# rev_001.net
KiCad netlist of a schematic drawn in EAGLE
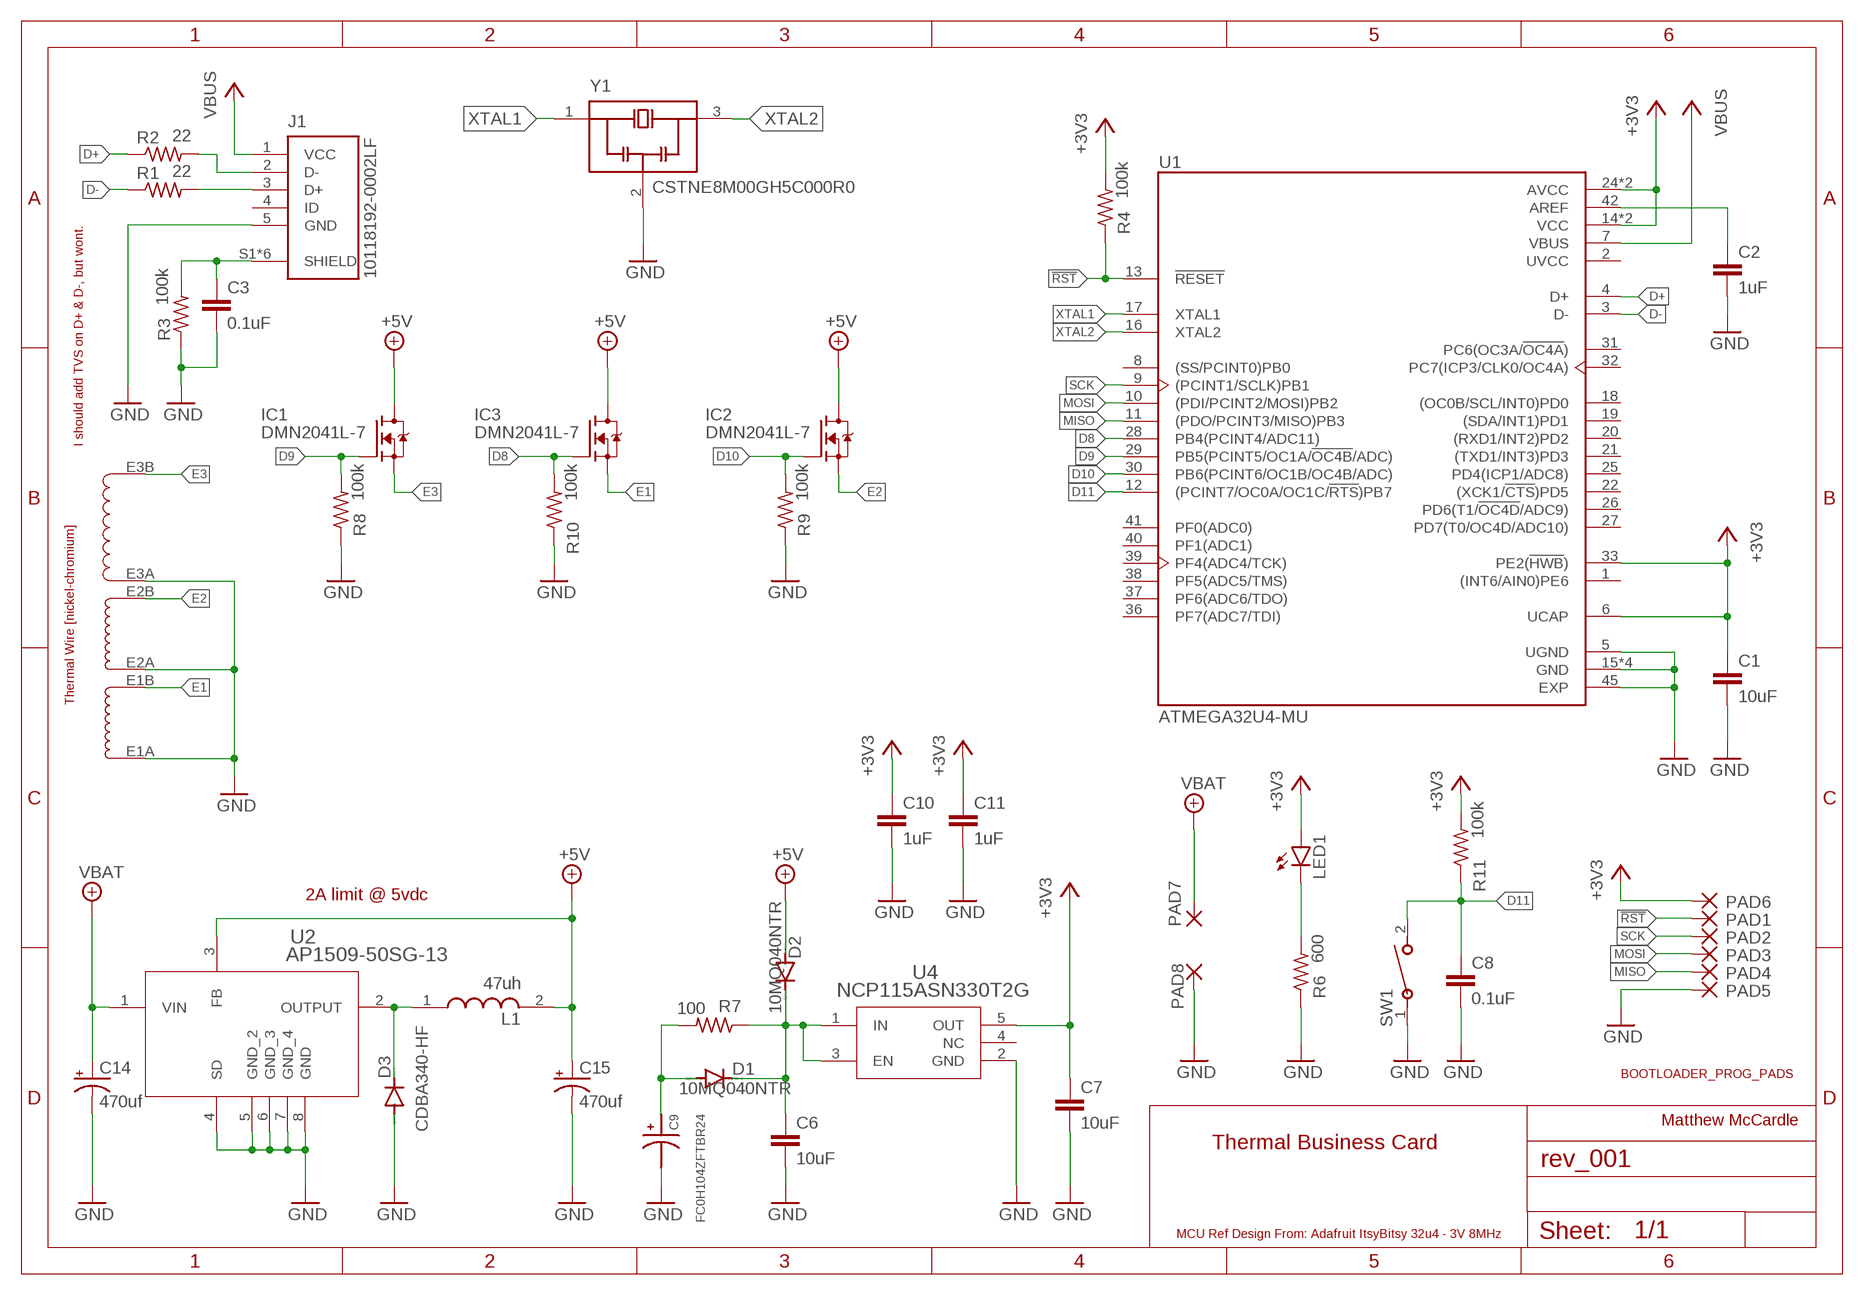
[diagram p0: schematic, sheet 1]

(export (version "E")
  (design (tool "Eeschema 10.0.6"))
  (components
    (comp (ref "C1")
      (value "10uF")
      (footprint "eagle-import:C0603")
      (libsource (lib "eagle-import") (part "C-EUC0603"))
    )
    (comp (ref "C2")
      (value "1uF")
      (footprint "eagle-import:C0603")
      (libsource (lib "eagle-import") (part "C-EUC0603"))
    )
    (comp (ref "C3")
      (value "0.1uF")
      (footprint "eagle-import:C0603")
      (libsource (lib "eagle-import") (part "C-EUC0603"))
    )
    (comp (ref "C6")
      (value "10uF")
      (footprint "eagle-import:C0603")
      (libsource (lib "eagle-import") (part "C-EUC0603"))
    )
    (comp (ref "C7")
      (value "10uF")
      (footprint "eagle-import:C0603")
      (libsource (lib "eagle-import") (part "C-EUC0603"))
    )
    (comp (ref "C8")
      (value "0.1uF")
      (footprint "eagle-import:C0603")
      (libsource (lib "eagle-import") (part "C-EUC0603"))
    )
    (comp (ref "C9")
      (value "FC0H104ZFTBR24")
      (footprint "eagle-import:CAPAE1080X580N")
      (fields (field (name "DIGI-KEY_PART_NUMBER") "399-10939-1-ND") (field (name "MF") "KEMET"))
      (libsource (lib "eagle-import") (part "FC0H104ZFTBR24"))
    )
    (comp (ref "C10")
      (value "1uF")
      (footprint "eagle-import:C0603")
      (libsource (lib "eagle-import") (part "C-EUC0603"))
    )
    (comp (ref "C11")
      (value "1uF")
      (footprint "eagle-import:C0603")
      (libsource (lib "eagle-import") (part "C-EUC0603"))
    )
    (comp (ref "C14")
      (value "470uf")
      (footprint "eagle-import:UD-4X5,8_NICHICON")
      (libsource (lib "eagle-import") (part "CPOL-USUD-4X5,8"))
    )
    (comp (ref "C15")
      (value "470uf")
      (footprint "eagle-import:UD-4X5,8_NICHICON")
      (libsource (lib "eagle-import") (part "CPOL-USUD-4X5,8"))
    )
    (comp (ref "D1")
      (value "10MQ040NTR")
      (footprint "eagle-import:DO-214AC")
      (libsource (lib "eagle-import") (part "DIODE-DO-214AC"))
    )
    (comp (ref "D2")
      (value "10MQ040NTR")
      (footprint "eagle-import:DO-214AC")
      (libsource (lib "eagle-import") (part "DIODE-DO-214AC"))
    )
    (comp (ref "D3")
      (value "CDBA340-HF")
      (footprint "eagle-import:DO-214AC")
      (libsource (lib "eagle-import") (part "DIODE-DO-214AC"))
    )
    (comp (ref "IC1")
      (value "DMN2041L-7")
      (footprint "eagle-import:SOT23")
      (libsource (lib "eagle-import") (part "DS31126"))
    )
    (comp (ref "IC2")
      (value "DMN2041L-7")
      (footprint "eagle-import:SOT23")
      (libsource (lib "eagle-import") (part "DS31126"))
    )
    (comp (ref "IC3")
      (value "DMN2041L-7")
      (footprint "eagle-import:SOT23")
      (libsource (lib "eagle-import") (part "DS31126"))
    )
    (comp (ref "J1")
      (value "10118192-0002LF")
      (footprint "eagle-import:AMPHENOL_10118192-0002LF")
      (fields (field (name "DIGI-KEY_PART_NUMBER") "609-5379-1-ND") (field (name "MF") "Amphenol ICC (FCI)"))
      (libsource (lib "eagle-import") (part "10118192-0002LF"))
    )
    (comp (ref "L1")
      (value "47uh")
      (footprint "eagle-import:WUERTH_ELEKTRONIK_7447714470_0")
      (fields (field (name "MF") "Wuerth Elektronik") (field (name "MPN") "7447714470"))
      (libsource (lib "eagle-import") (part "WUERTH_ELEKTRONIK_7447714470WUERTH_ELEKTRONIK_7447714470_0_0"))
    )
    (comp (ref "LED1")
      (value "LEDSML0603")
      (footprint "eagle-import:SML0603")
      (libsource (lib "eagle-import") (part "LEDSML0603"))
    )
    (comp (ref "NICR1")
      (value "HOT_WIRE")
      (footprint "eagle-import:LAYOUT_A")
      (libsource (lib "eagle-import") (part "HOT_WIRE"))
    )
    (comp (ref "PAD1")
      (value "WIREPADSMD1,27-254")
      (footprint "eagle-import:SMD1,27-2,54")
      (libsource (lib "eagle-import") (part "WIREPADSMD1,27-254"))
    )
    (comp (ref "PAD2")
      (value "WIREPADSMD1,27-254")
      (footprint "eagle-import:SMD1,27-2,54")
      (libsource (lib "eagle-import") (part "WIREPADSMD1,27-254"))
    )
    (comp (ref "PAD3")
      (value "WIREPADSMD1,27-254")
      (footprint "eagle-import:SMD1,27-2,54")
      (libsource (lib "eagle-import") (part "WIREPADSMD1,27-254"))
    )
    (comp (ref "PAD4")
      (value "WIREPADSMD1,27-254")
      (footprint "eagle-import:SMD1,27-2,54")
      (libsource (lib "eagle-import") (part "WIREPADSMD1,27-254"))
    )
    (comp (ref "PAD5")
      (value "WIREPADSMD1,27-254")
      (footprint "eagle-import:SMD1,27-2,54")
      (libsource (lib "eagle-import") (part "WIREPADSMD1,27-254"))
    )
    (comp (ref "PAD6")
      (value "WIREPADSMD1,27-254")
      (footprint "eagle-import:SMD1,27-2,54")
      (libsource (lib "eagle-import") (part "WIREPADSMD1,27-254"))
    )
    (comp (ref "PAD7")
      (value "WIREPAD2,54/0,9")
      (footprint "eagle-import:2,54_0,9")
      (libsource (lib "eagle-import") (part "WIREPAD2,54/0,9"))
    )
    (comp (ref "PAD8")
      (value "WIREPAD2,54/0,9")
      (footprint "eagle-import:2,54_0,9")
      (libsource (lib "eagle-import") (part "WIREPAD2,54/0,9"))
    )
    (comp (ref "R1")
      (value "22")
      (footprint "eagle-import:R0603")
      (libsource (lib "eagle-import") (part "R-US_R0603"))
    )
    (comp (ref "R2")
      (value "22")
      (footprint "eagle-import:R0603")
      (libsource (lib "eagle-import") (part "R-US_R0603"))
    )
    (comp (ref "R3")
      (value "100k")
      (footprint "eagle-import:R0603")
      (libsource (lib "eagle-import") (part "R-US_R0603"))
    )
    (comp (ref "R4")
      (value "100k")
      (footprint "eagle-import:R0603")
      (libsource (lib "eagle-import") (part "R-US_R0603"))
    )
    (comp (ref "R6")
      (value "600")
      (footprint "eagle-import:R0603")
      (libsource (lib "eagle-import") (part "R-US_R0603"))
    )
    (comp (ref "R7")
      (value "100")
      (footprint "eagle-import:R0603")
      (libsource (lib "eagle-import") (part "R-US_R0603"))
    )
    (comp (ref "R8")
      (value "100k")
      (footprint "eagle-import:R0603")
      (libsource (lib "eagle-import") (part "R-US_R0603"))
    )
    (comp (ref "R9")
      (value "100k")
      (footprint "eagle-import:R0603")
      (libsource (lib "eagle-import") (part "R-US_R0603"))
    )
    (comp (ref "R10")
      (value "100k")
      (footprint "eagle-import:R0603")
      (libsource (lib "eagle-import") (part "R-US_R0603"))
    )
    (comp (ref "R11")
      (value "100k")
      (footprint "eagle-import:R0603")
      (libsource (lib "eagle-import") (part "R-US_R0603"))
    )
    (comp (ref "SW1")
      (value "B3AL-1000P")
      (footprint "eagle-import:SW_B3AL_OMR")
      (fields (field (name "COPYRIGHT") "Copyright (C) 2021 Ultra Librarian. All rights reserved."))
      (libsource (lib "eagle-import") (part "B3AL-1000P"))
    )
    (comp (ref "U1")
      (value "ATMEGA32U4-MU")
      (footprint "eagle-import:QFN50P700X700X100-45N")
      (fields
        (field (name "DIGI-KEY_PART_NUMBER") "2156-ATMEGA32U4-MUR-ND")
        (field (name "MF") "Microchip Technology / Atmel")
      )
      (libsource (lib "eagle-import") (part "ATMEGA32U4-MU"))
    )
    (comp (ref "U2")
      (value "AP1509-50SG-13")
      (footprint "eagle-import:SOP-8L_DIO")
      (fields (field (name "COPYRIGHT") "Copyright (C) 2021 Ultra Librarian. All rights reserved."))
      (libsource (lib "eagle-import") (part "AP1509-50SG-13"))
    )
    (comp (ref "U4")
      (value "NCP115ASN330T2G")
      (footprint "eagle-import:TSOP-5-483-N_ONS")
      (fields (field (name "COPYRIGHT") "Copyright (C) 2021 Ultra Librarian. All rights reserved."))
      (libsource (lib "eagle-import") (part "NCP115ASN330T2G"))
    )
    (comp (ref "Y1")
      (value "CSTNE8M00GH5C000R0")
      (footprint "eagle-import:OSC_CSTNE8M00GH5C000R0")
      (fields (field (name "DIGI-KEY_PART_NUMBER") "490-17961-1-ND") (field (name "MF") "Murata"))
      (libsource (lib "eagle-import") (part "CSTNE8M00GH5C000R0"))
    )
  )
  (nets
    (net (code "1") (name "+3V3") (class "Default")
      (node (ref "C1") (pin "1") (pinfunction "1_1") (pintype "passive"))
      (node (ref "C10") (pin "1") (pinfunction "1_1") (pintype "passive"))
      (node (ref "C11") (pin "1") (pinfunction "1_1") (pintype "passive"))
      (node (ref "C7") (pin "1") (pinfunction "1_1") (pintype "passive"))
      (node (ref "LED1") (pin "A") (pinfunction "A_A") (pintype "passive"))
      (node (ref "PAD6") (pin "1") (pinfunction "P_1") (pintype "passive"))
      (node (ref "R11") (pin "2") (pinfunction "2_2") (pintype "passive"))
      (node (ref "R4") (pin "2") (pinfunction "2_2") (pintype "passive"))
      (node (ref "U1") (pin "14") (pinfunction "VCC_14") (pintype "power_in"))
      (node (ref "U1") (pin "24") (pinfunction "AVCC_24") (pintype "power_in"))
      (node (ref "U1") (pin "33") (pinfunction "PE2(~{HWB})_33") (pintype "bidirectional"))
      (node (ref "U1") (pin "34") (pinfunction "VCC_34") (pintype "power_in"))
      (node (ref "U1") (pin "44") (pinfunction "AVCC_44") (pintype "power_in"))
      (node (ref "U1") (pin "6") (pinfunction "UCAP_6") (pintype "passive"))
      (node (ref "U4") (pin "5") (pinfunction "OUT_5") (pintype "output"))
    )
    (net (code "2") (name "+5V") (class "Default")
      (node (ref "C15") (pin "+") (pinfunction "+_+") (pintype "passive"))
      (node (ref "D2") (pin "A") (pinfunction "A_A") (pintype "passive"))
      (node (ref "IC1") (pin "D") (pinfunction "D_D") (pintype "passive"))
      (node (ref "IC2") (pin "D") (pinfunction "D_D") (pintype "passive"))
      (node (ref "IC3") (pin "D") (pinfunction "D_D") (pintype "passive"))
      (node (ref "J1") (pin "1") (pinfunction "VCC_1") (pintype "power_in"))
      (node (ref "L1") (pin "2") (pinfunction "2_2") (pintype "passive"))
      (node (ref "U1") (pin "7") (pinfunction "VBUS_7") (pintype "power_in"))
      (node (ref "U2") (pin "3") (pinfunction "FB_3") (pintype "output"))
    )
    (net (code "3") (name "/UVCC") (class "Default")
      (node (ref "U1") (pin "2") (pinfunction "UVCC_2") (pintype "power_in"))
    )
    (net (code "4") (name "/~{RST}") (class "Default")
      (node (ref "PAD1") (pin "1") (pinfunction "P_1") (pintype "passive"))
      (node (ref "R4") (pin "1") (pinfunction "1_1") (pintype "passive"))
      (node (ref "U1") (pin "13") (pinfunction "~{RESET}_13") (pintype "input"))
    )
    (net (code "5") (name "D+") (class "Default")
      (node (ref "R2") (pin "1") (pinfunction "1_1") (pintype "passive"))
      (node (ref "U1") (pin "4") (pinfunction "D+_4") (pintype "bidirectional"))
    )
    (net (code "6") (name "D-") (class "Default")
      (node (ref "R1") (pin "1") (pinfunction "1_1") (pintype "passive"))
      (node (ref "U1") (pin "3") (pinfunction "D-_3") (pintype "bidirectional"))
    )
    (net (code "7") (name "D8") (class "Default")
      (node (ref "IC3") (pin "G") (pinfunction "G_G") (pintype "passive"))
      (node (ref "R10") (pin "2") (pinfunction "2_2") (pintype "passive"))
      (node (ref "U1") (pin "28") (pinfunction "PB4(PCINT4/ADC11)_28") (pintype "bidirectional"))
    )
    (net (code "8") (name "D9") (class "Default")
      (node (ref "IC1") (pin "G") (pinfunction "G_G") (pintype "passive"))
      (node (ref "R8") (pin "2") (pinfunction "2_2") (pintype "passive"))
      (node (ref "U1") (pin "29") (pinfunction "PB5(PCINT5/OC1A/~{OC4B}/ADC)_29") (pintype "bidirectional"))
    )
    (net (code "9") (name "D10") (class "Default")
      (node (ref "IC2") (pin "G") (pinfunction "G_G") (pintype "passive"))
      (node (ref "R9") (pin "2") (pinfunction "2_2") (pintype "passive"))
      (node (ref "U1") (pin "30") (pinfunction "PB6(PCINT6/OC1B/OC4B/ADC)_30") (pintype "bidirectional"))
    )
    (net (code "10") (name "D11") (class "Default")
      (node (ref "C8") (pin "1") (pinfunction "1_1") (pintype "passive"))
      (node (ref "R11") (pin "1") (pinfunction "1_1") (pintype "passive"))
      (node (ref "SW1") (pin "2") (pinfunction "2_2") (pintype "passive"))
      (node (ref "U1") (pin "12") (pinfunction "(PCINT7/OC0A/OC1C/~{RTS})PB7_12") (pintype "bidirectional"))
    )
    (net (code "11") (name "E1") (class "Default")
      (node (ref "IC3") (pin "S") (pinfunction "S_S") (pintype "passive"))
      (node (ref "NICR1") (pin "E1B") (pinfunction "P$2_E1B") (pintype "bidirectional"))
    )
    (net (code "12") (name "E2") (class "Default")
      (node (ref "IC2") (pin "S") (pinfunction "S_S") (pintype "passive"))
      (node (ref "NICR1") (pin "E2B") (pinfunction "P$2_E2B") (pintype "bidirectional"))
    )
    (net (code "13") (name "E3") (class "Default")
      (node (ref "IC1") (pin "S") (pinfunction "S_S") (pintype "passive"))
      (node (ref "NICR1") (pin "E3B") (pinfunction "P$2_E3B") (pintype "bidirectional"))
    )
    (net (code "14") (name "GND") (class "Default")
      (node (ref "C1") (pin "2") (pinfunction "2_2") (pintype "passive"))
      (node (ref "C10") (pin "2") (pinfunction "2_2") (pintype "passive"))
      (node (ref "C11") (pin "2") (pinfunction "2_2") (pintype "passive"))
      (node (ref "C14") (pin "-") (pinfunction "-_-") (pintype "passive"))
      (node (ref "C15") (pin "-") (pinfunction "-_-") (pintype "passive"))
      (node (ref "C2") (pin "2") (pinfunction "2_2") (pintype "passive"))
      (node (ref "C3") (pin "2") (pinfunction "2_2") (pintype "passive"))
      (node (ref "C6") (pin "2") (pinfunction "2_2") (pintype "passive"))
      (node (ref "C7") (pin "2") (pinfunction "2_2") (pintype "passive"))
      (node (ref "C8") (pin "2") (pinfunction "2_2") (pintype "passive"))
      (node (ref "C9") (pin "2") (pinfunction "2_2") (pintype "passive"))
      (node (ref "D3") (pin "A") (pinfunction "A_A") (pintype "passive"))
      (node (ref "J1") (pin "5") (pinfunction "GND_5") (pintype "power_in"))
      (node (ref "NICR1") (pin "E1A") (pinfunction "P$1_E1A") (pintype "bidirectional"))
      (node (ref "NICR1") (pin "E2A") (pinfunction "P$1_E2A") (pintype "bidirectional"))
      (node (ref "NICR1") (pin "E3A") (pinfunction "P$1_E3A") (pintype "bidirectional"))
      (node (ref "PAD5") (pin "1") (pinfunction "P_1") (pintype "passive"))
      (node (ref "PAD8") (pin "1") (pinfunction "P_1") (pintype "passive"))
      (node (ref "R10") (pin "1") (pinfunction "1_1") (pintype "passive"))
      (node (ref "R3") (pin "1") (pinfunction "1_1") (pintype "passive"))
      (node (ref "R6") (pin "1") (pinfunction "1_1") (pintype "passive"))
      (node (ref "R8") (pin "1") (pinfunction "1_1") (pintype "passive"))
      (node (ref "R9") (pin "1") (pinfunction "1_1") (pintype "passive"))
      (node (ref "SW1") (pin "1") (pinfunction "1_1") (pintype "passive"))
      (node (ref "U1") (pin "15") (pinfunction "GND_15") (pintype "power_in"))
      (node (ref "U1") (pin "23") (pinfunction "GND_23") (pintype "power_in"))
      (node (ref "U1") (pin "35") (pinfunction "GND_35") (pintype "power_in"))
      (node (ref "U1") (pin "43") (pinfunction "GND_43") (pintype "power_in"))
      (node (ref "U1") (pin "45") (pinfunction "EXP_45") (pintype "passive"))
      (node (ref "U1") (pin "5") (pinfunction "UGND_5") (pintype "power_in"))
      (node (ref "U2") (pin "4") (pinfunction "SD_4") (pintype "passive"))
      (node (ref "U2") (pin "5") (pinfunction "GND_2_5") (pintype "power_in"))
      (node (ref "U2") (pin "6") (pinfunction "GND_3_6") (pintype "power_in"))
      (node (ref "U2") (pin "7") (pinfunction "GND_4_7") (pintype "power_in"))
      (node (ref "U2") (pin "8") (pinfunction "GND_8") (pintype "power_in"))
      (node (ref "U4") (pin "2") (pinfunction "GND_2") (pintype "passive"))
      (node (ref "Y1") (pin "2") (pinfunction "GND_2") (pintype "power_in"))
    )
    (net (code "15") (name "MISO") (class "Default")
      (node (ref "PAD4") (pin "1") (pinfunction "P_1") (pintype "passive"))
      (node (ref "U1") (pin "11") (pinfunction "(PDO/PCINT3/MISO)PB3_11") (pintype "bidirectional"))
    )
    (net (code "16") (name "MOSI") (class "Default")
      (node (ref "PAD3") (pin "1") (pinfunction "P_1") (pintype "passive"))
      (node (ref "U1") (pin "10") (pinfunction "(PDI/PCINT2/MOSI)PB2_10") (pintype "bidirectional"))
    )
    (net (code "17") (name "Net-(C3-Pad1)") (class "Default")
      (node (ref "C3") (pin "1") (pinfunction "1_1") (pintype "passive"))
      (node (ref "J1") (pin "S1") (pinfunction "SHIELD_S1") (pintype "passive"))
      (node (ref "J1") (pin "S2") (pinfunction "SHIELD_S2") (pintype "passive"))
      (node (ref "J1") (pin "S3") (pinfunction "SHIELD_S3") (pintype "passive"))
      (node (ref "J1") (pin "S4") (pinfunction "SHIELD_S4") (pintype "passive"))
      (node (ref "J1") (pin "S5") (pinfunction "SHIELD_S5") (pintype "passive"))
      (node (ref "J1") (pin "S6") (pinfunction "SHIELD_S6") (pintype "passive"))
      (node (ref "R3") (pin "2") (pinfunction "2_2") (pintype "passive"))
    )
    (net (code "18") (name "Net-(C9-Pad1)") (class "Default")
      (node (ref "C9") (pin "1") (pinfunction "1_1") (pintype "passive"))
      (node (ref "D1") (pin "A") (pinfunction "A_A") (pintype "passive"))
      (node (ref "R7") (pin "2") (pinfunction "2_2") (pintype "passive"))
    )
    (net (code "19") (name "Net-(J1-D+)") (class "Default")
      (node (ref "J1") (pin "3") (pinfunction "D+_3") (pintype "bidirectional"))
      (node (ref "R1") (pin "2") (pinfunction "2_2") (pintype "passive"))
    )
    (net (code "20") (name "Net-(J1-D-)") (class "Default")
      (node (ref "J1") (pin "2") (pinfunction "D-_2") (pintype "bidirectional"))
      (node (ref "R2") (pin "2") (pinfunction "2_2") (pintype "passive"))
    )
    (net (code "21") (name "Net-(LED1-PadC)") (class "Default")
      (node (ref "LED1") (pin "C") (pinfunction "C_C") (pintype "passive"))
      (node (ref "R6") (pin "2") (pinfunction "2_2") (pintype "passive"))
    )
    (net (code "22") (name "Net-(U1-AREF)") (class "Default")
      (node (ref "C2") (pin "1") (pinfunction "1_1") (pintype "passive"))
      (node (ref "U1") (pin "42") (pinfunction "AREF_42") (pintype "power_in"))
    )
    (net (code "23") (name "Net-(U2-OUTPUT)") (class "Default")
      (node (ref "D3") (pin "C") (pinfunction "C_C") (pintype "passive"))
      (node (ref "L1") (pin "1") (pinfunction "1_1") (pintype "passive"))
      (node (ref "U2") (pin "2") (pinfunction "OUTPUT_2") (pintype "output"))
    )
    (net (code "24") (name "Net-(U4-EN)") (class "Default")
      (node (ref "C6") (pin "1") (pinfunction "1_1") (pintype "passive"))
      (node (ref "D1") (pin "C") (pinfunction "C_C") (pintype "passive"))
      (node (ref "D2") (pin "C") (pinfunction "C_C") (pintype "passive"))
      (node (ref "R7") (pin "1") (pinfunction "1_1") (pintype "passive"))
      (node (ref "U4") (pin "1") (pinfunction "IN_1") (pintype "input"))
      (node (ref "U4") (pin "3") (pinfunction "EN_3") (pintype "passive"))
    )
    (net (code "25") (name "SCK") (class "Default")
      (node (ref "PAD2") (pin "1") (pinfunction "P_1") (pintype "passive"))
      (node (ref "U1") (pin "9") (pinfunction "(PCINT1/SCLK)PB1_9") (pintype "bidirectional"))
    )
    (net (code "26") (name "VBAT") (class "Default")
      (node (ref "C14") (pin "+") (pinfunction "+_+") (pintype "passive"))
      (node (ref "PAD7") (pin "1") (pinfunction "P_1") (pintype "passive"))
      (node (ref "U2") (pin "1") (pinfunction "VIN_1") (pintype "input"))
    )
    (net (code "27") (name "XTAL1") (class "Default")
      (node (ref "U1") (pin "17") (pinfunction "XTAL1_17") (pintype "input"))
      (node (ref "Y1") (pin "1") (pinfunction "IN_1") (pintype "input"))
    )
    (net (code "28") (name "XTAL2") (class "Default")
      (node (ref "U1") (pin "16") (pinfunction "XTAL2_16") (pintype "output"))
      (node (ref "Y1") (pin "3") (pinfunction "OUT_3") (pintype "output"))
    )
    (net (code "29") (name "unconnected-(J1-ID-Pad4)") (class "Default")
      (node (ref "J1") (pin "4") (pinfunction "ID_4") (pintype "bidirectional"))
    )
    (net (code "30") (name "unconnected-(U1-(INT6{slash}AIN0)PE6-Pad1)") (class "Default")
      (node (ref "U1") (pin "1") (pinfunction "(INT6/AIN0)PE6_1") (pintype "bidirectional"))
    )
    (net (code "31") (name "unconnected-(U1-(OC0B{slash}SCL{slash}INT0)PD0-Pad18)") (class "Default")
      (node (ref "U1") (pin "18") (pinfunction "(OC0B/SCL/INT0)PD0_18") (pintype "bidirectional"))
    )
    (net (code "32") (name "unconnected-(U1-(RXD1{slash}INT2)PD2-Pad20)") (class "Default")
      (node (ref "U1") (pin "20") (pinfunction "(RXD1/INT2)PD2_20") (pintype "bidirectional"))
    )
    (net (code "33") (name "unconnected-(U1-(SDA{slash}INT1)PD1-Pad19)") (class "Default")
      (node (ref "U1") (pin "19") (pinfunction "(SDA/INT1)PD1_19") (pintype "bidirectional"))
    )
    (net (code "34") (name "unconnected-(U1-(SS{slash}PCINT0)PB0-Pad8)") (class "Default")
      (node (ref "U1") (pin "8") (pinfunction "(SS/PCINT0)PB0_8") (pintype "bidirectional"))
    )
    (net (code "35") (name "unconnected-(U1-(TXD1{slash}INT3)PD3-Pad21)") (class "Default")
      (node (ref "U1") (pin "21") (pinfunction "(TXD1/INT3)PD3_21") (pintype "bidirectional"))
    )
    (net (code "36") (name "unconnected-(U1-(XCK1{slash}~{CTS})PD5-Pad22)") (class "Default")
      (node (ref "U1") (pin "22") (pinfunction "(XCK1/~{CTS})PD5_22") (pintype "bidirectional"))
    )
    (net (code "37") (name "unconnected-(U1-PC6(OC3A{slash}~{OC4A})-Pad31)") (class "Default")
      (node (ref "U1") (pin "31") (pinfunction "PC6(OC3A/~{OC4A})_31") (pintype "bidirectional"))
    )
    (net (code "38") (name "unconnected-(U1-PC7(ICP3{slash}CLK0{slash}OC4A)-Pad32)") (class "Default")
      (node (ref "U1") (pin "32") (pinfunction "PC7(ICP3/CLK0/OC4A)_32") (pintype "bidirectional"))
    )
    (net (code "39") (name "unconnected-(U1-PD4(ICP1{slash}ADC8)-Pad25)") (class "Default")
      (node (ref "U1") (pin "25") (pinfunction "PD4(ICP1/ADC8)_25") (pintype "bidirectional"))
    )
    (net (code "40") (name "unconnected-(U1-PD6(T1{slash}~{OC4D}{slash}ADC9)-Pad26)") (class "Default")
      (node (ref "U1") (pin "26") (pinfunction "PD6(T1/~{OC4D}/ADC9)_26") (pintype "bidirectional"))
    )
    (net (code "41") (name "unconnected-(U1-PD7(T0{slash}OC4D{slash}ADC10)-Pad27)") (class "Default")
      (node (ref "U1") (pin "27") (pinfunction "PD7(T0/OC4D/ADC10)_27") (pintype "bidirectional"))
    )
    (net (code "42") (name "unconnected-(U1-PF0(ADC0)-Pad41)") (class "Default")
      (node (ref "U1") (pin "41") (pinfunction "PF0(ADC0)_41") (pintype "bidirectional"))
    )
    (net (code "43") (name "unconnected-(U1-PF1(ADC1)-Pad40)") (class "Default")
      (node (ref "U1") (pin "40") (pinfunction "PF1(ADC1)_40") (pintype "bidirectional"))
    )
    (net (code "44") (name "unconnected-(U1-PF4(ADC4{slash}TCK)-Pad39)") (class "Default")
      (node (ref "U1") (pin "39") (pinfunction "PF4(ADC4/TCK)_39") (pintype "bidirectional"))
    )
    (net (code "45") (name "unconnected-(U1-PF5(ADC5{slash}TMS)-Pad38)") (class "Default")
      (node (ref "U1") (pin "38") (pinfunction "PF5(ADC5/TMS)_38") (pintype "bidirectional"))
    )
    (net (code "46") (name "unconnected-(U1-PF6(ADC6{slash}TDO)-Pad37)") (class "Default")
      (node (ref "U1") (pin "37") (pinfunction "PF6(ADC6/TDO)_37") (pintype "bidirectional"))
    )
    (net (code "47") (name "unconnected-(U1-PF7(ADC7{slash}TDI)-Pad36)") (class "Default")
      (node (ref "U1") (pin "36") (pinfunction "PF7(ADC7/TDI)_36") (pintype "bidirectional"))
    )
    (net (code "48") (name "unconnected-(U4-NC-Pad4)") (class "Default")
      (node (ref "U4") (pin "4") (pinfunction "NC_4") (pintype "no_connect"))
    )
  )
)
